# connectors.net
KiCad netlist of a schematic drawn in Altium Designer
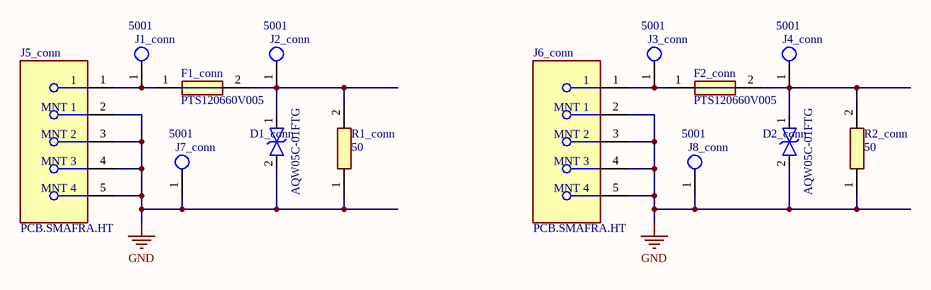
[diagram p0: connectors.SchDoc]

(export (version "E")
  (design (tool "Eeschema 10.0.6"))
  (components
    (comp (ref "D1_conn")
      (value "AQW05C-01FTG")
      (footprint "SOD2613X100N")
      (description "TVS Diode (Bi-directional)")
      (fields (field (name "MOUSER PART NUMBER") "576-AQW05C-01FTG"))
      (libsource (lib "za_koncar") (part "AQW05C-01FTG"))
    )
    (comp (ref "D2_conn")
      (value "AQW05C-01FTG")
      (footprint "SOD2613X100N")
      (description "TVS Diode (Bi-directional)")
      (fields (field (name "MOUSER PART NUMBER") "576-AQW05C-01FTG"))
      (libsource (lib "za_koncar") (part "AQW05C-01FTG"))
    )
    (comp (ref "F1_conn")
      (value "PTS120660V005")
      (footprint "FUSC3216X90N")
      (description "Fuse")
      (fields (field (name "MOUSER PART NUMBER") "504-PTS120660V005"))
      (libsource (lib "za_koncar") (part "PTS120660V005"))
    )
    (comp (ref "F2_conn")
      (value "PTS120660V005")
      (footprint "FUSC3216X90N")
      (description "Fuse")
      (fields (field (name "MOUSER PART NUMBER") "504-PTS120660V005"))
      (libsource (lib "za_koncar") (part "PTS120660V005"))
    )
    (comp (ref "J1_conn")
      (value "5001")
      (footprint "FP-5001-MFG")
      (description "PC TEST POINT MINIATURE BLACK")
      (libsource (lib "za_koncar") (part "CMP-2000-05181-2"))
    )
    (comp (ref "J2_conn")
      (value "5001")
      (footprint "FP-5001-MFG")
      (description "PC TEST POINT MINIATURE BLACK")
      (libsource (lib "za_koncar") (part "CMP-2000-05181-2"))
    )
    (comp (ref "J3_conn")
      (value "5001")
      (footprint "FP-5001-MFG")
      (description "PC TEST POINT MINIATURE BLACK")
      (libsource (lib "za_koncar") (part "CMP-2000-05181-2"))
    )
    (comp (ref "J4_conn")
      (value "5001")
      (footprint "FP-5001-MFG")
      (description "PC TEST POINT MINIATURE BLACK")
      (libsource (lib "za_koncar") (part "CMP-2000-05181-2"))
    )
    (comp (ref "J5_conn")
      (value "PCB.SMAFRA.HT")
      (footprint "FP-PCB_SMAFRA_HT-MFG")
      (description "CONN SMA JACK R/A 50OHM PCB")
      (libsource (lib "za_koncar") (part "CMP-111093-000003-1"))
    )
    (comp (ref "J6_conn")
      (value "PCB.SMAFRA.HT")
      (footprint "FP-PCB_SMAFRA_HT-MFG")
      (description "CONN SMA JACK R/A 50OHM PCB")
      (libsource (lib "za_koncar") (part "CMP-111093-000003-1"))
    )
    (comp (ref "J7_conn")
      (value "5001")
      (footprint "FP-5001-MFG")
      (description "PC TEST POINT MINIATURE BLACK")
      (libsource (lib "za_koncar") (part "CMP-2000-05181-2"))
    )
    (comp (ref "J8_conn")
      (value "5001")
      (footprint "FP-5001-MFG")
      (description "PC TEST POINT MINIATURE BLACK")
      (libsource (lib "za_koncar") (part "CMP-2000-05181-2"))
    )
    (comp (ref "R1_conn")
      (value "50")
      (footprint "RESC6332X65N")
      (description "Resistor")
      (fields (field (name "MANUFACTURER_PART_NUMBER") "RNCL2512FT50R0"))
      (libsource (lib "za_koncar") (part "RNCL2512FT50R0"))
    )
    (comp (ref "R2_conn")
      (value "50")
      (footprint "RESC6332X65N")
      (description "Resistor")
      (fields (field (name "MANUFACTURER_PART_NUMBER") "RNCL2512FT50R0"))
      (libsource (lib "za_koncar") (part "RNCL2512FT50R0"))
    )
  )
  (nets
    (net (code "1") (name "GND") (class "Default")
      (node (ref "D1_conn") (pin "2") (pinfunction "2_2") (pintype "passive"))
      (node (ref "D2_conn") (pin "2") (pinfunction "2_2") (pintype "passive"))
      (node (ref "J5_conn") (pin "2") (pinfunction "MNT_1_2") (pintype "passive"))
      (node (ref "J5_conn") (pin "3") (pinfunction "MNT_2_3") (pintype "passive"))
      (node (ref "J5_conn") (pin "4") (pinfunction "MNT_3_4") (pintype "passive"))
      (node (ref "J5_conn") (pin "5") (pinfunction "MNT_4_5") (pintype "passive"))
      (node (ref "J6_conn") (pin "2") (pinfunction "MNT_1_2") (pintype "passive"))
      (node (ref "J6_conn") (pin "3") (pinfunction "MNT_2_3") (pintype "passive"))
      (node (ref "J6_conn") (pin "4") (pinfunction "MNT_3_4") (pintype "passive"))
      (node (ref "J6_conn") (pin "5") (pinfunction "MNT_4_5") (pintype "passive"))
      (node (ref "J7_conn") (pin "1") (pinfunction "1_1") (pintype "passive"))
      (node (ref "J8_conn") (pin "1") (pinfunction "1_1") (pintype "passive"))
      (node (ref "R1_conn") (pin "1") (pinfunction "1_1") (pintype "passive"))
      (node (ref "R2_conn") (pin "1") (pinfunction "1_1") (pintype "passive"))
    )
    (net (code "2") (name "Net-(D1_conn-Pad1)") (class "Default")
      (node (ref "D1_conn") (pin "1") (pinfunction "1_1") (pintype "passive"))
      (node (ref "F1_conn") (pin "2") (pinfunction "2_2") (pintype "passive"))
      (node (ref "J2_conn") (pin "1") (pinfunction "1_1") (pintype "passive"))
      (node (ref "R1_conn") (pin "2") (pinfunction "2_2") (pintype "passive"))
    )
    (net (code "3") (name "Net-(D2_conn-Pad1)") (class "Default")
      (node (ref "D2_conn") (pin "1") (pinfunction "1_1") (pintype "passive"))
      (node (ref "F2_conn") (pin "2") (pinfunction "2_2") (pintype "passive"))
      (node (ref "J4_conn") (pin "1") (pinfunction "1_1") (pintype "passive"))
      (node (ref "R2_conn") (pin "2") (pinfunction "2_2") (pintype "passive"))
    )
    (net (code "4") (name "Net-(F1_conn-Pad1)") (class "Default")
      (node (ref "F1_conn") (pin "1") (pinfunction "1_1") (pintype "passive"))
      (node (ref "J1_conn") (pin "1") (pinfunction "1_1") (pintype "passive"))
      (node (ref "J5_conn") (pin "1") (pinfunction "1_1") (pintype "passive"))
    )
    (net (code "5") (name "Net-(F2_conn-Pad1)") (class "Default")
      (node (ref "F2_conn") (pin "1") (pinfunction "1_1") (pintype "passive"))
      (node (ref "J3_conn") (pin "1") (pinfunction "1_1") (pintype "passive"))
      (node (ref "J6_conn") (pin "1") (pinfunction "1_1") (pintype "passive"))
    )
  )
)
